# pool-monitor.net
KiCad netlist of a schematic drawn in EAGLE
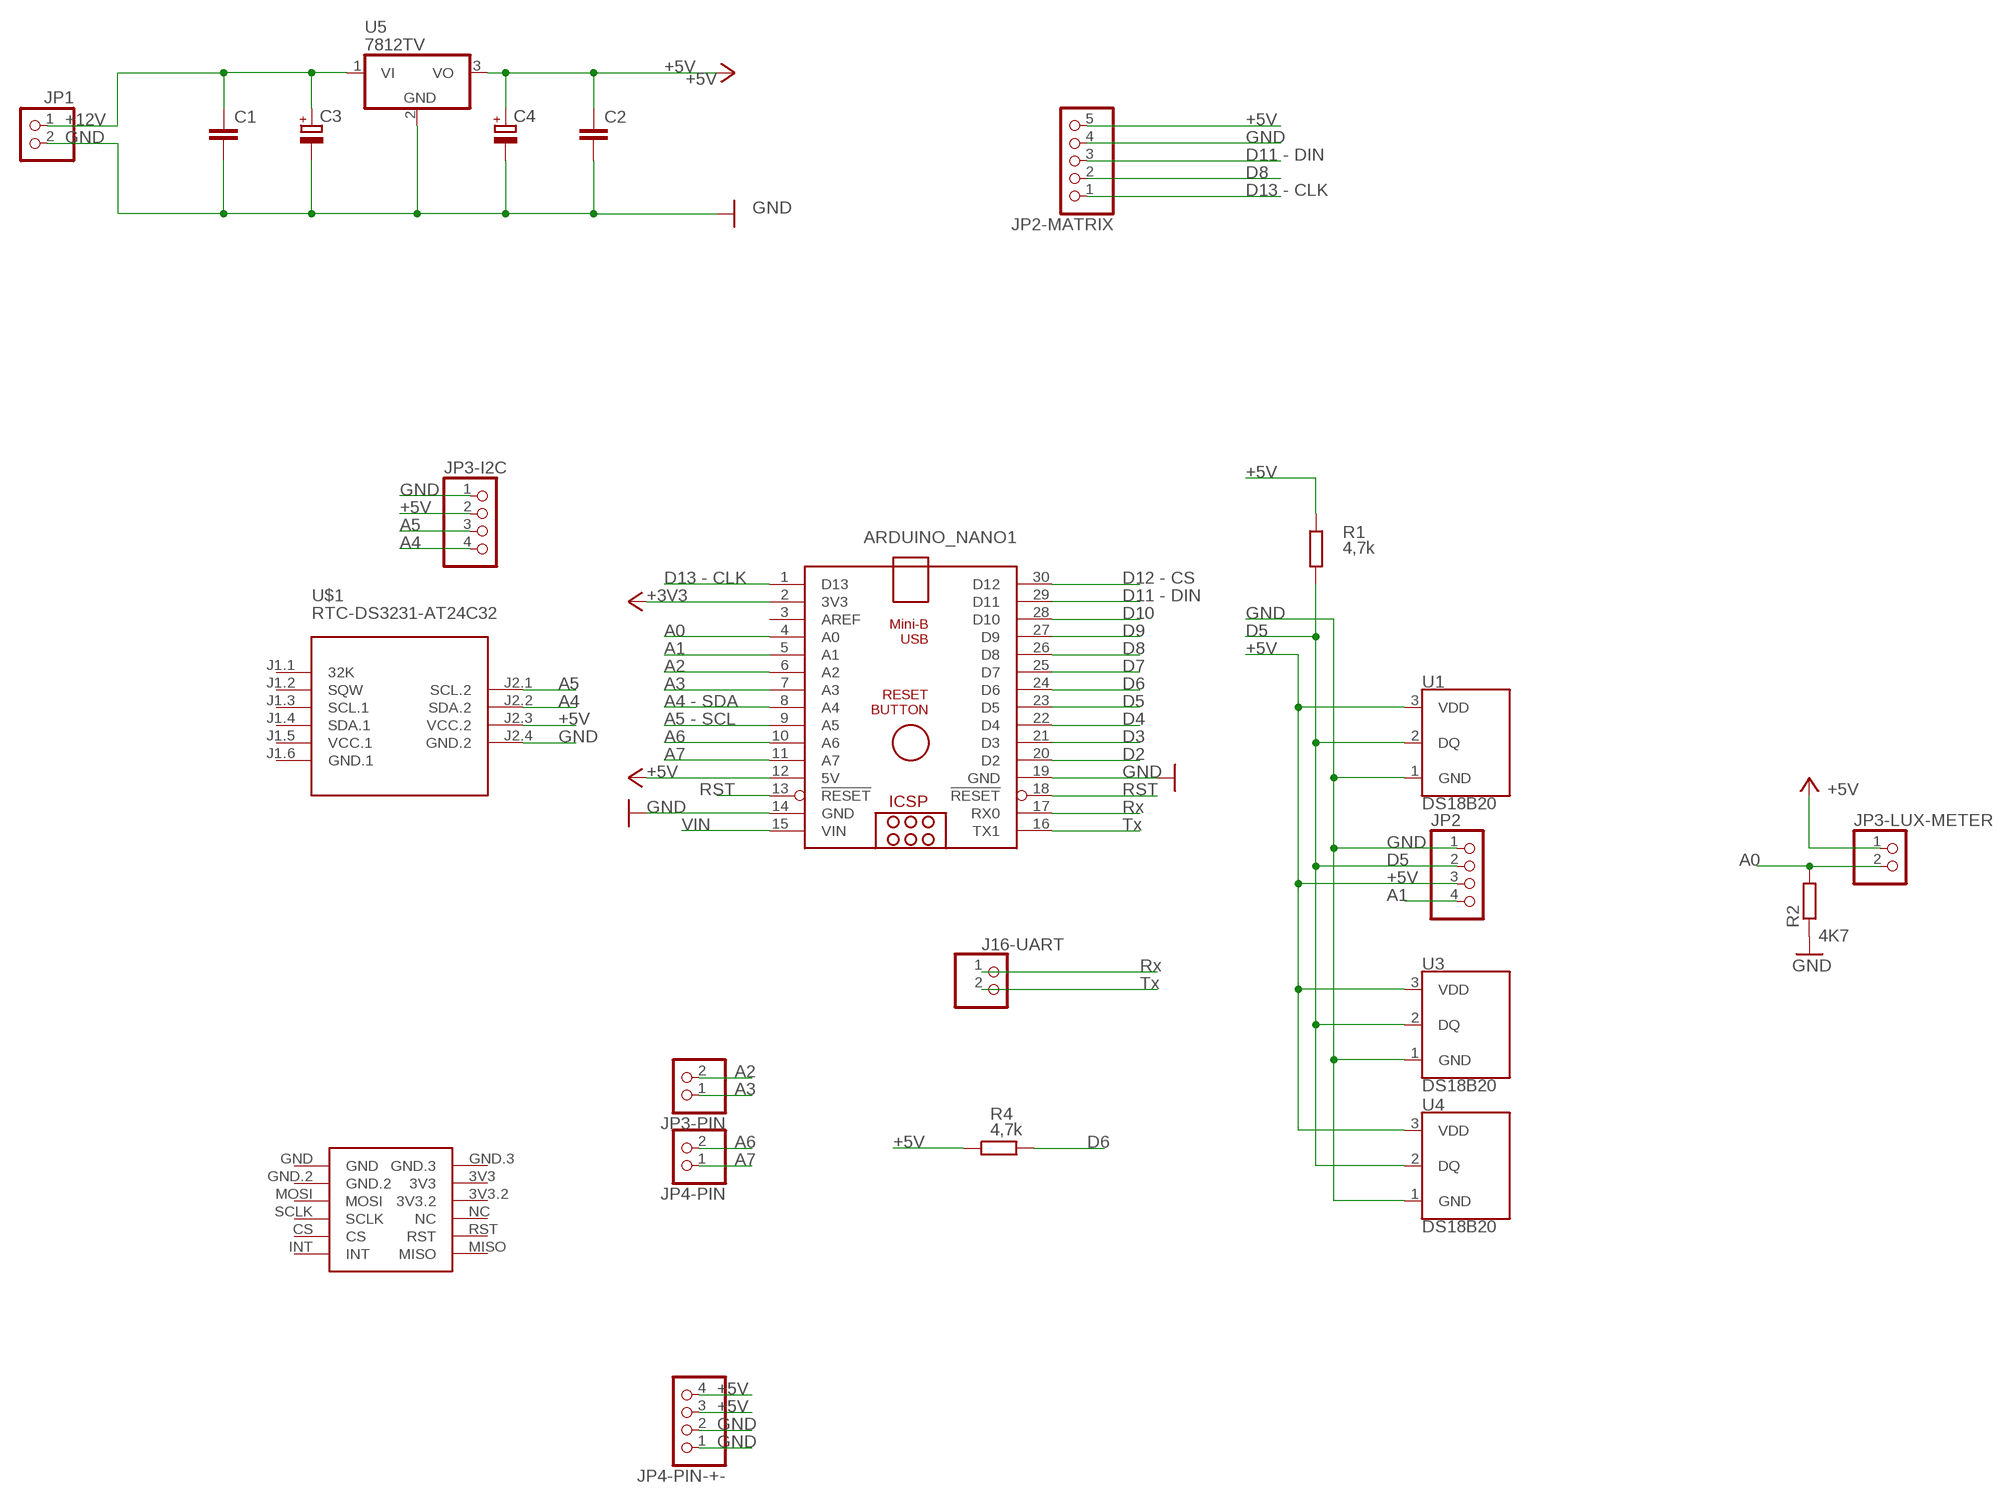
[diagram p0: schematic, sheet 1]

(export (version "E")
  (design (tool "Eeschema 10.0.6"))
  (components
    (comp (ref "ARDUINO_NANO1")
      (value "ARDUINO_NANO")
      (footprint "eagle-import:ARDUINO_NANO")
      (libsource (lib "eagle-import") (part "ARDUINO_NANO"))
    )
    (comp (ref "C1")
      (value "C-EU025-025X050")
      (footprint "eagle-import:C025-025X050")
      (libsource (lib "eagle-import") (part "C-EU025-025X050"))
    )
    (comp (ref "C2")
      (value "C-EU025-025X050")
      (footprint "eagle-import:C025-025X050")
      (libsource (lib "eagle-import") (part "C-EU025-025X050"))
    )
    (comp (ref "C3")
      (value "CPOL-EUE2-5")
      (footprint "eagle-import:E2-5")
      (libsource (lib "eagle-import") (part "CPOL-EUE2-5"))
    )
    (comp (ref "C4")
      (value "CPOL-EUE2-5")
      (footprint "eagle-import:E2-5")
      (libsource (lib "eagle-import") (part "CPOL-EUE2-5"))
    )
    (comp (ref "J16-UART")
      (value "PINHD-1X2")
      (footprint "eagle-import:1X02")
      (libsource (lib "eagle-import") (part "PINHD-1X2"))
    )
    (comp (ref "JP1")
      (value "PINHD-1X2")
      (footprint "eagle-import:1X02")
      (libsource (lib "eagle-import") (part "PINHD-1X2"))
    )
    (comp (ref "JP2")
      (value "PINHD-1X4")
      (footprint "eagle-import:1X04")
      (libsource (lib "eagle-import") (part "PINHD-1X4"))
    )
    (comp (ref "JP2-MATRIX")
      (value "PINHD-1X5")
      (footprint "eagle-import:1X05")
      (libsource (lib "eagle-import") (part "PINHD-1X5"))
    )
    (comp (ref "JP3-I2C")
      (value "PINHD-1X4")
      (footprint "eagle-import:1X04")
      (libsource (lib "eagle-import") (part "PINHD-1X4"))
    )
    (comp (ref "JP3-LUX-METER")
      (value "PINHD-1X2")
      (footprint "eagle-import:1X02")
      (libsource (lib "eagle-import") (part "PINHD-1X2"))
    )
    (comp (ref "JP3-PIN")
      (value "PINHD-1X2")
      (footprint "eagle-import:1X02")
      (libsource (lib "eagle-import") (part "PINHD-1X2"))
    )
    (comp (ref "JP4-PIN")
      (value "PINHD-1X2")
      (footprint "eagle-import:1X02")
      (libsource (lib "eagle-import") (part "PINHD-1X2"))
    )
    (comp (ref "JP4-PIN-+-")
      (value "PINHD-1X4")
      (footprint "eagle-import:1X04")
      (libsource (lib "eagle-import") (part "PINHD-1X4"))
    )
    (comp (ref "R1")
      (value "4,7k")
      (footprint "eagle-import:0204_7")
      (libsource (lib "eagle-import") (part "R-EU_0204/7"))
    )
    (comp (ref "R2")
      (value "4K7")
      (footprint "eagle-import:0207_10")
      (libsource (lib "eagle-import") (part "rcl_334_R-EU_0207/10"))
    )
    (comp (ref "R4")
      (value "4,7k")
      (footprint "eagle-import:0204_7")
      (libsource (lib "eagle-import") (part "R-EU_0204/7"))
    )
    (comp (ref "U$1")
      (value "RTC-DS3231-AT24C32")
      (footprint "eagle-import:RTC-DS3231-AT24C32")
      (libsource (lib "eagle-import") (part "RTC-DS3231-AT24C32"))
    )
    (comp (ref "U$2")
      (value "MINI_W5500")
      (footprint "eagle-import:MINI_W5500")
      (libsource (lib "eagle-import") (part "MINI_W5500"))
    )
    (comp (ref "U1")
      (value "DS18B20")
      (footprint "eagle-import:TO-92-AMMO")
      (libsource (lib "eagle-import") (part "DS18B20"))
    )
    (comp (ref "U3")
      (value "DS18B20")
      (footprint "eagle-import:TO-92-AMMO")
      (libsource (lib "eagle-import") (part "DS18B20"))
    )
    (comp (ref "U4")
      (value "DS18B20")
      (footprint "eagle-import:TO-92-AMMO")
      (libsource (lib "eagle-import") (part "DS18B20"))
    )
    (comp (ref "U5")
      (value "7812TV")
      (footprint "eagle-import:TO220V")
      (libsource (lib "eagle-import") (part "78TV12"))
    )
  )
  (nets
    (net (code "1") (name "+3V3") (class "Default")
      (node (ref "ARDUINO_NANO1") (pin "2") (pinfunction "3V3_2") (pintype "output"))
    )
    (net (code "2") (name "+5V") (class "Default")
      (node (ref "ARDUINO_NANO1") (pin "12") (pinfunction "5V_12") (pintype "power_in"))
      (node (ref "C2") (pin "1") (pinfunction "1_1") (pintype "passive"))
      (node (ref "C4") (pin "+") (pinfunction "+_+") (pintype "passive"))
      (node (ref "JP2") (pin "3") (pinfunction "3_3") (pintype "passive"))
      (node (ref "JP2-MATRIX") (pin "5") (pinfunction "5_5") (pintype "passive"))
      (node (ref "JP3-I2C") (pin "2") (pinfunction "2_2") (pintype "passive"))
      (node (ref "JP3-LUX-METER") (pin "1") (pinfunction "1_1") (pintype "passive"))
      (node (ref "JP4-PIN-+-") (pin "3") (pinfunction "3_3") (pintype "passive"))
      (node (ref "JP4-PIN-+-") (pin "4") (pinfunction "4_4") (pintype "passive"))
      (node (ref "R1") (pin "1") (pinfunction "1_1") (pintype "passive"))
      (node (ref "R4") (pin "1") (pinfunction "1_1") (pintype "passive"))
      (node (ref "U$1") (pin "J2.3") (pinfunction "VCC.2_J2.3") (pintype "power_in"))
      (node (ref "U1") (pin "3") (pinfunction "VDD_3") (pintype "power_in"))
      (node (ref "U3") (pin "3") (pinfunction "VDD_3") (pintype "power_in"))
      (node (ref "U4") (pin "3") (pinfunction "VDD_3") (pintype "power_in"))
      (node (ref "U5") (pin "3") (pinfunction "VO_3") (pintype "passive"))
    )
    (net (code "3") (name "/+12V") (class "Default")
      (node (ref "C1") (pin "1") (pinfunction "1_1") (pintype "passive"))
      (node (ref "C3") (pin "+") (pinfunction "+_+") (pintype "passive"))
      (node (ref "JP1") (pin "1") (pinfunction "1_1") (pintype "passive"))
      (node (ref "U5") (pin "1") (pinfunction "VI_1") (pintype "input"))
    )
    (net (code "4") (name "/A0") (class "Default")
      (node (ref "ARDUINO_NANO1") (pin "4") (pinfunction "A0_4") (pintype "bidirectional"))
      (node (ref "JP3-LUX-METER") (pin "2") (pinfunction "2_2") (pintype "passive"))
      (node (ref "R2") (pin "2") (pinfunction "2_2") (pintype "passive"))
    )
    (net (code "5") (name "/A1") (class "Default")
      (node (ref "ARDUINO_NANO1") (pin "5") (pinfunction "A1_5") (pintype "bidirectional"))
      (node (ref "JP2") (pin "4") (pinfunction "4_4") (pintype "passive"))
    )
    (net (code "6") (name "/A2") (class "Default")
      (node (ref "ARDUINO_NANO1") (pin "6") (pinfunction "A2_6") (pintype "bidirectional"))
      (node (ref "JP3-PIN") (pin "2") (pinfunction "2_2") (pintype "passive"))
    )
    (net (code "7") (name "/A3") (class "Default")
      (node (ref "ARDUINO_NANO1") (pin "7") (pinfunction "A3_7") (pintype "bidirectional"))
      (node (ref "JP3-PIN") (pin "1") (pinfunction "1_1") (pintype "passive"))
    )
    (net (code "8") (name "/A4") (class "Default")
      (node (ref "ARDUINO_NANO1") (pin "8") (pinfunction "A4_8") (pintype "bidirectional"))
      (node (ref "JP3-I2C") (pin "4") (pinfunction "4_4") (pintype "passive"))
      (node (ref "U$1") (pin "J2.2") (pinfunction "SDA.2_J2.2") (pintype "bidirectional"))
    )
    (net (code "9") (name "/A5") (class "Default")
      (node (ref "ARDUINO_NANO1") (pin "9") (pinfunction "A5_9") (pintype "bidirectional"))
      (node (ref "JP3-I2C") (pin "3") (pinfunction "3_3") (pintype "passive"))
      (node (ref "U$1") (pin "J2.1") (pinfunction "SCL.2_J2.1") (pintype "bidirectional"))
    )
    (net (code "10") (name "/A6") (class "Default")
      (node (ref "ARDUINO_NANO1") (pin "10") (pinfunction "A6_10") (pintype "bidirectional"))
      (node (ref "JP4-PIN") (pin "2") (pinfunction "2_2") (pintype "passive"))
    )
    (net (code "11") (name "/A7") (class "Default")
      (node (ref "ARDUINO_NANO1") (pin "11") (pinfunction "A7_11") (pintype "bidirectional"))
      (node (ref "JP4-PIN") (pin "1") (pinfunction "1_1") (pintype "passive"))
    )
    (net (code "12") (name "/D5") (class "Default")
      (node (ref "ARDUINO_NANO1") (pin "23") (pinfunction "D5_23") (pintype "bidirectional"))
      (node (ref "JP2") (pin "2") (pinfunction "2_2") (pintype "passive"))
      (node (ref "R1") (pin "2") (pinfunction "2_2") (pintype "passive"))
      (node (ref "U1") (pin "2") (pinfunction "DQ_2") (pintype "bidirectional"))
      (node (ref "U3") (pin "2") (pinfunction "DQ_2") (pintype "bidirectional"))
      (node (ref "U4") (pin "2") (pinfunction "DQ_2") (pintype "bidirectional"))
    )
    (net (code "13") (name "/D6") (class "Default")
      (node (ref "ARDUINO_NANO1") (pin "24") (pinfunction "D6_24") (pintype "bidirectional"))
      (node (ref "R4") (pin "2") (pinfunction "2_2") (pintype "passive"))
    )
    (net (code "14") (name "/D8") (class "Default")
      (node (ref "ARDUINO_NANO1") (pin "26") (pinfunction "D8_26") (pintype "bidirectional"))
      (node (ref "JP2-MATRIX") (pin "2") (pinfunction "2_2") (pintype "passive"))
    )
    (net (code "15") (name "/D11") (class "Default")
      (node (ref "ARDUINO_NANO1") (pin "29") (pinfunction "D11_29") (pintype "bidirectional"))
      (node (ref "JP2-MATRIX") (pin "3") (pinfunction "3_3") (pintype "passive"))
    )
    (net (code "16") (name "/D13") (class "Default")
      (node (ref "ARDUINO_NANO1") (pin "1") (pinfunction "D13_1") (pintype "bidirectional"))
      (node (ref "JP2-MATRIX") (pin "1") (pinfunction "1_1") (pintype "passive"))
    )
    (net (code "17") (name "/GND.1") (class "Default")
      (node (ref "U$1") (pin "J1.6") (pinfunction "GND.1_J1.6") (pintype "power_in"))
    )
    (net (code "18") (name "/RST") (class "Default")
      (node (ref "ARDUINO_NANO1") (pin "13") (pinfunction "~{RESET}_13") (pintype "input"))
      (node (ref "ARDUINO_NANO1") (pin "18") (pinfunction "~{RESET}_18") (pintype "input"))
    )
    (net (code "19") (name "/RX") (class "Default")
      (node (ref "ARDUINO_NANO1") (pin "17") (pinfunction "RX0_17") (pintype "bidirectional"))
      (node (ref "J16-UART") (pin "1") (pinfunction "1_1") (pintype "passive"))
    )
    (net (code "20") (name "/TX") (class "Default")
      (node (ref "ARDUINO_NANO1") (pin "16") (pinfunction "TX1_16") (pintype "bidirectional"))
      (node (ref "J16-UART") (pin "2") (pinfunction "2_2") (pintype "passive"))
    )
    (net (code "21") (name "/VCC.1") (class "Default")
      (node (ref "U$1") (pin "J1.5") (pinfunction "VCC.1_J1.5") (pintype "power_in"))
    )
    (net (code "22") (name "GND") (class "Default")
      (node (ref "ARDUINO_NANO1") (pin "14") (pinfunction "GND_14") (pintype "power_in"))
      (node (ref "ARDUINO_NANO1") (pin "19") (pinfunction "GND_19") (pintype "power_in"))
      (node (ref "C1") (pin "2") (pinfunction "2_2") (pintype "passive"))
      (node (ref "C2") (pin "2") (pinfunction "2_2") (pintype "passive"))
      (node (ref "C3") (pin "-") (pinfunction "-_-") (pintype "passive"))
      (node (ref "C4") (pin "-") (pinfunction "-_-") (pintype "passive"))
      (node (ref "JP1") (pin "2") (pinfunction "2_2") (pintype "passive"))
      (node (ref "JP2") (pin "1") (pinfunction "1_1") (pintype "passive"))
      (node (ref "JP2-MATRIX") (pin "4") (pinfunction "4_4") (pintype "passive"))
      (node (ref "JP3-I2C") (pin "1") (pinfunction "1_1") (pintype "passive"))
      (node (ref "JP4-PIN-+-") (pin "1") (pinfunction "1_1") (pintype "passive"))
      (node (ref "JP4-PIN-+-") (pin "2") (pinfunction "2_2") (pintype "passive"))
      (node (ref "R2") (pin "1") (pinfunction "1_1") (pintype "passive"))
      (node (ref "U$1") (pin "J2.4") (pinfunction "GND.2_J2.4") (pintype "power_in"))
      (node (ref "U1") (pin "1") (pinfunction "GND_1") (pintype "power_in"))
      (node (ref "U3") (pin "1") (pinfunction "GND_1") (pintype "power_in"))
      (node (ref "U4") (pin "1") (pinfunction "GND_1") (pintype "power_in"))
      (node (ref "U5") (pin "2") (pinfunction "GND_2") (pintype "passive"))
    )
    (net (code "23") (name "unconnected-(ARDUINO_NANO1-AREF-Pad3)") (class "Default")
      (node (ref "ARDUINO_NANO1") (pin "3") (pinfunction "AREF_3") (pintype "input"))
    )
    (net (code "24") (name "unconnected-(ARDUINO_NANO1-D2-Pad20)") (class "Default")
      (node (ref "ARDUINO_NANO1") (pin "20") (pinfunction "D2_20") (pintype "bidirectional"))
    )
    (net (code "25") (name "unconnected-(ARDUINO_NANO1-D3-Pad21)") (class "Default")
      (node (ref "ARDUINO_NANO1") (pin "21") (pinfunction "D3_21") (pintype "bidirectional"))
    )
    (net (code "26") (name "unconnected-(ARDUINO_NANO1-D4-Pad22)") (class "Default")
      (node (ref "ARDUINO_NANO1") (pin "22") (pinfunction "D4_22") (pintype "bidirectional"))
    )
    (net (code "27") (name "unconnected-(ARDUINO_NANO1-D7-Pad25)") (class "Default")
      (node (ref "ARDUINO_NANO1") (pin "25") (pinfunction "D7_25") (pintype "bidirectional"))
    )
    (net (code "28") (name "unconnected-(ARDUINO_NANO1-D9-Pad27)") (class "Default")
      (node (ref "ARDUINO_NANO1") (pin "27") (pinfunction "D9_27") (pintype "bidirectional"))
    )
    (net (code "29") (name "unconnected-(ARDUINO_NANO1-D10-Pad28)") (class "Default")
      (node (ref "ARDUINO_NANO1") (pin "28") (pinfunction "D10_28") (pintype "bidirectional"))
    )
    (net (code "30") (name "unconnected-(ARDUINO_NANO1-D12-Pad30)") (class "Default")
      (node (ref "ARDUINO_NANO1") (pin "30") (pinfunction "D12_30") (pintype "bidirectional"))
    )
    (net (code "31") (name "unconnected-(ARDUINO_NANO1-VIN-Pad15)") (class "Default")
      (node (ref "ARDUINO_NANO1") (pin "15") (pinfunction "VIN_15") (pintype "power_in"))
    )
    (net (code "32") (name "unconnected-(U$1-32K-PadJ1.1)") (class "Default")
      (node (ref "U$1") (pin "J1.1") (pinfunction "32K_J1.1") (pintype "bidirectional"))
    )
    (net (code "33") (name "unconnected-(U$1-SCL.1-PadJ1.3)") (class "Default")
      (node (ref "U$1") (pin "J1.3") (pinfunction "SCL.1_J1.3") (pintype "bidirectional"))
    )
    (net (code "34") (name "unconnected-(U$1-SDA.1-PadJ1.4)") (class "Default")
      (node (ref "U$1") (pin "J1.4") (pinfunction "SDA.1_J1.4") (pintype "bidirectional"))
    )
    (net (code "35") (name "unconnected-(U$1-SQW-PadJ1.2)") (class "Default")
      (node (ref "U$1") (pin "J1.2") (pinfunction "SQW_J1.2") (pintype "bidirectional"))
    )
    (net (code "36") (name "unconnected-(U$2-Pad3V3)") (class "Default")
      (node (ref "U$2") (pin "3V3") (pinfunction "3V3_3V3") (pintype "bidirectional"))
    )
    (net (code "37") (name "unconnected-(U$2-Pad3V3.2)") (class "Default")
      (node (ref "U$2") (pin "3V3.2") (pinfunction "3V3.2_3V3.2") (pintype "bidirectional"))
    )
    (net (code "38") (name "unconnected-(U$2-PadCS)") (class "Default")
      (node (ref "U$2") (pin "CS") (pinfunction "CS_CS") (pintype "bidirectional"))
    )
    (net (code "39") (name "unconnected-(U$2-PadGND)") (class "Default")
      (node (ref "U$2") (pin "GND") (pinfunction "GND_GND") (pintype "bidirectional"))
    )
    (net (code "40") (name "unconnected-(U$2-PadGND.2)") (class "Default")
      (node (ref "U$2") (pin "GND.2") (pinfunction "GND.2_GND.2") (pintype "bidirectional"))
    )
    (net (code "41") (name "unconnected-(U$2-PadGND.3)") (class "Default")
      (node (ref "U$2") (pin "GND.3") (pinfunction "GND.3_GND.3") (pintype "bidirectional"))
    )
    (net (code "42") (name "unconnected-(U$2-PadINT)") (class "Default")
      (node (ref "U$2") (pin "INT") (pinfunction "INT_INT") (pintype "bidirectional"))
    )
    (net (code "43") (name "unconnected-(U$2-PadMISO)") (class "Default")
      (node (ref "U$2") (pin "MISO") (pinfunction "MISO_MISO") (pintype "bidirectional"))
    )
    (net (code "44") (name "unconnected-(U$2-PadMOSI)") (class "Default")
      (node (ref "U$2") (pin "MOSI") (pinfunction "MOSI_MOSI") (pintype "bidirectional"))
    )
    (net (code "45") (name "unconnected-(U$2-PadNC)") (class "Default")
      (node (ref "U$2") (pin "NC") (pinfunction "NC_NC") (pintype "bidirectional"))
    )
    (net (code "46") (name "unconnected-(U$2-PadRST)") (class "Default")
      (node (ref "U$2") (pin "RST") (pinfunction "RST_RST") (pintype "bidirectional"))
    )
    (net (code "47") (name "unconnected-(U$2-PadSCLK)") (class "Default")
      (node (ref "U$2") (pin "SCLK") (pinfunction "SCLK_SCLK") (pintype "bidirectional"))
    )
  )
)
